# arm_femur_wLED_stemma.net
KiCad netlist of a schematic drawn in EAGLE
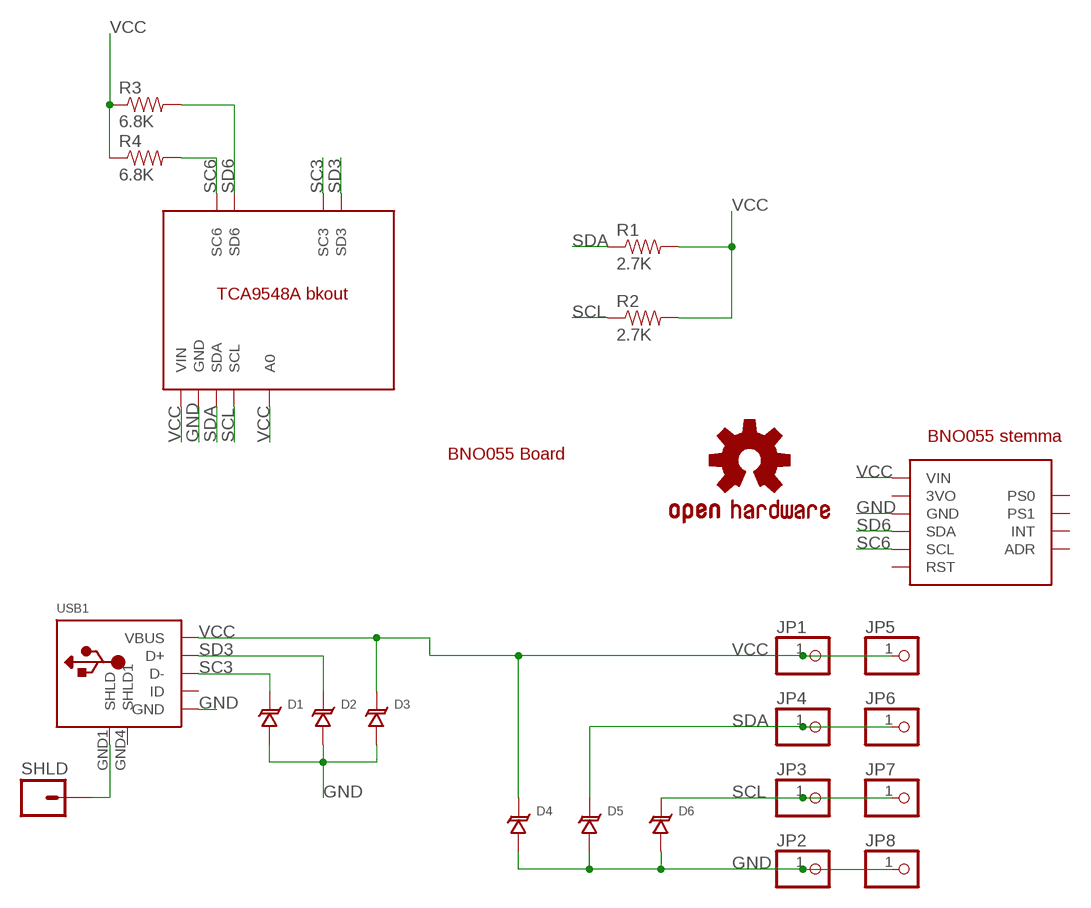
[diagram p0: schematic, sheet 1]

(export (version "E")
  (design (tool "Eeschema 10.0.6"))
  (components
    (comp (ref "D1")
      (value "TVS_DIODE_SOD723")
      (footprint "eagle-import:SOD723")
      (libsource (lib "eagle-import") (part "TVS_DIODE_SOD723"))
    )
    (comp (ref "D2")
      (value "TVS_DIODE_SOD723")
      (footprint "eagle-import:SOD723")
      (libsource (lib "eagle-import") (part "TVS_DIODE_SOD723"))
    )
    (comp (ref "D3")
      (value "TVS_DIODE_SOD723")
      (footprint "eagle-import:SOD723")
      (libsource (lib "eagle-import") (part "TVS_DIODE_SOD723"))
    )
    (comp (ref "D4")
      (value "TVS_DIODE_SOD723")
      (footprint "eagle-import:SOD723")
      (libsource (lib "eagle-import") (part "TVS_DIODE_SOD723"))
    )
    (comp (ref "D5")
      (value "TVS_DIODE_SOD723")
      (footprint "eagle-import:SOD723")
      (libsource (lib "eagle-import") (part "TVS_DIODE_SOD723"))
    )
    (comp (ref "D6")
      (value "TVS_DIODE_SOD723")
      (footprint "eagle-import:SOD723")
      (libsource (lib "eagle-import") (part "TVS_DIODE_SOD723"))
    )
    (comp (ref "JP1")
      (value "PINHD-1X1CB")
      (footprint "eagle-import:1X01-CLEANBIG")
      (libsource (lib "eagle-import") (part "PINHD-1X1CB"))
    )
    (comp (ref "JP2")
      (value "PINHD-1X1CB")
      (footprint "eagle-import:1X01-CLEANBIG")
      (libsource (lib "eagle-import") (part "PINHD-1X1CB"))
    )
    (comp (ref "JP3")
      (value "PINHD-1X1CB")
      (footprint "eagle-import:1X01-CLEANBIG")
      (libsource (lib "eagle-import") (part "PINHD-1X1CB"))
    )
    (comp (ref "JP4")
      (value "PINHD-1X1CB")
      (footprint "eagle-import:1X01-CLEANBIG")
      (libsource (lib "eagle-import") (part "PINHD-1X1CB"))
    )
    (comp (ref "JP5")
      (value "PINHD-1X1CB")
      (footprint "eagle-import:1X01-CLEANBIG")
      (libsource (lib "eagle-import") (part "PINHD-1X1CB"))
    )
    (comp (ref "JP6")
      (value "PINHD-1X1CB")
      (footprint "eagle-import:1X01-CLEANBIG")
      (libsource (lib "eagle-import") (part "PINHD-1X1CB"))
    )
    (comp (ref "JP7")
      (value "PINHD-1X1CB")
      (footprint "eagle-import:1X01-CLEANBIG")
      (libsource (lib "eagle-import") (part "PINHD-1X1CB"))
    )
    (comp (ref "JP8")
      (value "PINHD-1X1CB")
      (footprint "eagle-import:1X01-CLEANBIG")
      (libsource (lib "eagle-import") (part "PINHD-1X1CB"))
    )
    (comp (ref "LOGO1")
      (value "OSHW-LOGOM")
      (footprint "eagle-import:OSHW-LOGO-M")
      (libsource (lib "eagle-import") (part "OSHW-LOGOM"))
    )
    (comp (ref "R1")
      (value "2.7K")
      (footprint "eagle-import:AXIAL-0.3")
      (libsource (lib "eagle-import") (part "RESISTORAXIAL-0.3"))
    )
    (comp (ref "R2")
      (value "2.7K")
      (footprint "eagle-import:AXIAL-0.3")
      (libsource (lib "eagle-import") (part "RESISTORAXIAL-0.3"))
    )
    (comp (ref "R3")
      (value "6.8K")
      (footprint "eagle-import:AXIAL-0.3")
      (libsource (lib "eagle-import") (part "RESISTORAXIAL-0.3"))
    )
    (comp (ref "R4")
      (value "6.8K")
      (footprint "eagle-import:AXIAL-0.3")
      (libsource (lib "eagle-import") (part "RESISTORAXIAL-0.3"))
    )
    (comp (ref "SHLD")
      (value "M01PTH")
      (footprint "eagle-import:1X01")
      (libsource (lib "eagle-import") (part "M01PTH"))
    )
    (comp (ref "U$2")
      (value "TCA9548_ARM_FEMUR")
      (footprint "eagle-import:TCA9548_ARM_FEMUR")
      (libsource (lib "eagle-import") (part "TCA9548_ARM_FEMUR"))
    )
    (comp (ref "U$3")
      (value "BNO_055_STEMMA")
      (footprint "eagle-import:BNO_STEMMA")
      (libsource (lib "eagle-import") (part "BNO_055_STEMMA"))
    )
    (comp (ref "USB1")
      (value "USB")
      (footprint "eagle-import:USB-MINIB-THM-MOLEX_NOSLK")
      (libsource (lib "eagle-import") (part "USB"))
    )
  )
  (nets
    (net (code "1") (name "/GND") (class "Default")
      (node (ref "D1") (pin "A") (pinfunction "A_A") (pintype "passive"))
      (node (ref "D2") (pin "A") (pinfunction "A_A") (pintype "passive"))
      (node (ref "D3") (pin "A") (pinfunction "A_A") (pintype "passive"))
      (node (ref "D4") (pin "A") (pinfunction "A_A") (pintype "passive"))
      (node (ref "D5") (pin "A") (pinfunction "A_A") (pintype "passive"))
      (node (ref "D6") (pin "A") (pinfunction "A_A") (pintype "passive"))
      (node (ref "JP2") (pin "1") (pinfunction "1_1") (pintype "passive"))
      (node (ref "JP8") (pin "1") (pinfunction "1_1") (pintype "passive"))
      (node (ref "U$2") (pin "GND") (pinfunction "GND_GND") (pintype "bidirectional"))
      (node (ref "U$3") (pin "GND") (pinfunction "GND_GND") (pintype "bidirectional"))
      (node (ref "USB1") (pin "GND") (pinfunction "GND_GND") (pintype "power_in"))
    )
    (net (code "2") (name "/SC3") (class "Default")
      (node (ref "D1") (pin "C") (pinfunction "C_C") (pintype "passive"))
      (node (ref "U$2") (pin "SC3") (pinfunction "SC3_SC3") (pintype "bidirectional"))
      (node (ref "USB1") (pin "D-") (pinfunction "D-_D-") (pintype "bidirectional"))
    )
    (net (code "3") (name "/SC6") (class "Default")
      (node (ref "R4") (pin "P$2") (pinfunction "2_P$2") (pintype "passive"))
      (node (ref "U$2") (pin "SC6") (pinfunction "SC6_SC6") (pintype "bidirectional"))
      (node (ref "U$3") (pin "SCL") (pinfunction "SCL_SCL") (pintype "bidirectional"))
    )
    (net (code "4") (name "/SCL") (class "Default")
      (node (ref "D6") (pin "C") (pinfunction "C_C") (pintype "passive"))
      (node (ref "JP3") (pin "1") (pinfunction "1_1") (pintype "passive"))
      (node (ref "JP7") (pin "1") (pinfunction "1_1") (pintype "passive"))
      (node (ref "R2") (pin "P$1") (pinfunction "1_P$1") (pintype "passive"))
      (node (ref "U$2") (pin "SCL") (pinfunction "SCL_SCL") (pintype "bidirectional"))
    )
    (net (code "5") (name "/SD3") (class "Default")
      (node (ref "D2") (pin "C") (pinfunction "C_C") (pintype "passive"))
      (node (ref "U$2") (pin "SD3") (pinfunction "SD3_SD3") (pintype "bidirectional"))
      (node (ref "USB1") (pin "D+") (pinfunction "D+_D+") (pintype "bidirectional"))
    )
    (net (code "6") (name "/SD6") (class "Default")
      (node (ref "R3") (pin "P$2") (pinfunction "2_P$2") (pintype "passive"))
      (node (ref "U$2") (pin "SD6") (pinfunction "SD6_SD6") (pintype "bidirectional"))
      (node (ref "U$3") (pin "SDA") (pinfunction "SDA_SDA") (pintype "bidirectional"))
    )
    (net (code "7") (name "/SDA") (class "Default")
      (node (ref "D5") (pin "C") (pinfunction "C_C") (pintype "passive"))
      (node (ref "JP4") (pin "1") (pinfunction "1_1") (pintype "passive"))
      (node (ref "JP6") (pin "1") (pinfunction "1_1") (pintype "passive"))
      (node (ref "R1") (pin "P$1") (pinfunction "1_P$1") (pintype "passive"))
      (node (ref "U$2") (pin "SDA") (pinfunction "SDA_SDA") (pintype "bidirectional"))
    )
    (net (code "8") (name "/VCC") (class "Default")
      (node (ref "D3") (pin "C") (pinfunction "C_C") (pintype "passive"))
      (node (ref "D4") (pin "C") (pinfunction "C_C") (pintype "passive"))
      (node (ref "JP1") (pin "1") (pinfunction "1_1") (pintype "passive"))
      (node (ref "JP5") (pin "1") (pinfunction "1_1") (pintype "passive"))
      (node (ref "R1") (pin "P$2") (pinfunction "2_P$2") (pintype "passive"))
      (node (ref "R2") (pin "P$2") (pinfunction "2_P$2") (pintype "passive"))
      (node (ref "R3") (pin "P$1") (pinfunction "1_P$1") (pintype "passive"))
      (node (ref "R4") (pin "P$1") (pinfunction "1_P$1") (pintype "passive"))
      (node (ref "U$2") (pin "A0") (pinfunction "A0_A0") (pintype "bidirectional"))
      (node (ref "U$2") (pin "VIN") (pinfunction "VIN_VIN") (pintype "bidirectional"))
      (node (ref "U$3") (pin "VIN") (pinfunction "VIN_VIN") (pintype "bidirectional"))
      (node (ref "USB1") (pin "VBUS") (pinfunction "VBUS_VBUS") (pintype "power_in"))
    )
    (net (code "9") (name "Net-(USB1-SHLD)") (class "Default")
      (node (ref "SHLD") (pin "1") (pinfunction "1_1") (pintype "passive"))
      (node (ref "USB1") (pin "GND1") (pinfunction "SHLD_GND1") (pintype "bidirectional"))
    )
    (net (code "10") (name "unconnected-(U$3-Pad3VO)") (class "Default")
      (node (ref "U$3") (pin "3VO") (pinfunction "3VO_3VO") (pintype "bidirectional"))
    )
    (net (code "11") (name "unconnected-(U$3-PadADR)") (class "Default")
      (node (ref "U$3") (pin "ADR") (pinfunction "ADR_ADR") (pintype "bidirectional"))
    )
    (net (code "12") (name "unconnected-(U$3-PadINT)") (class "Default")
      (node (ref "U$3") (pin "INT") (pinfunction "INT_INT") (pintype "bidirectional"))
    )
    (net (code "13") (name "unconnected-(U$3-PadPS0)") (class "Default")
      (node (ref "U$3") (pin "PS0") (pinfunction "PS0_PS0") (pintype "bidirectional"))
    )
    (net (code "14") (name "unconnected-(U$3-PadPS1)") (class "Default")
      (node (ref "U$3") (pin "PS1") (pinfunction "PS1_PS1") (pintype "bidirectional"))
    )
    (net (code "15") (name "unconnected-(U$3-PadRST)") (class "Default")
      (node (ref "U$3") (pin "RST") (pinfunction "RST_RST") (pintype "bidirectional"))
    )
    (net (code "16") (name "unconnected-(USB1-PadID)") (class "Default")
      (node (ref "USB1") (pin "ID") (pinfunction "ID_ID") (pintype "bidirectional"))
    )
    (net (code "17") (name "unconnected-(USB1-SHLD1-PadGND4)") (class "Default")
      (node (ref "USB1") (pin "GND4") (pinfunction "SHLD1_GND4") (pintype "bidirectional"))
    )
  )
)
